# ADC.net
KiCad netlist of a schematic drawn in Altium Designer
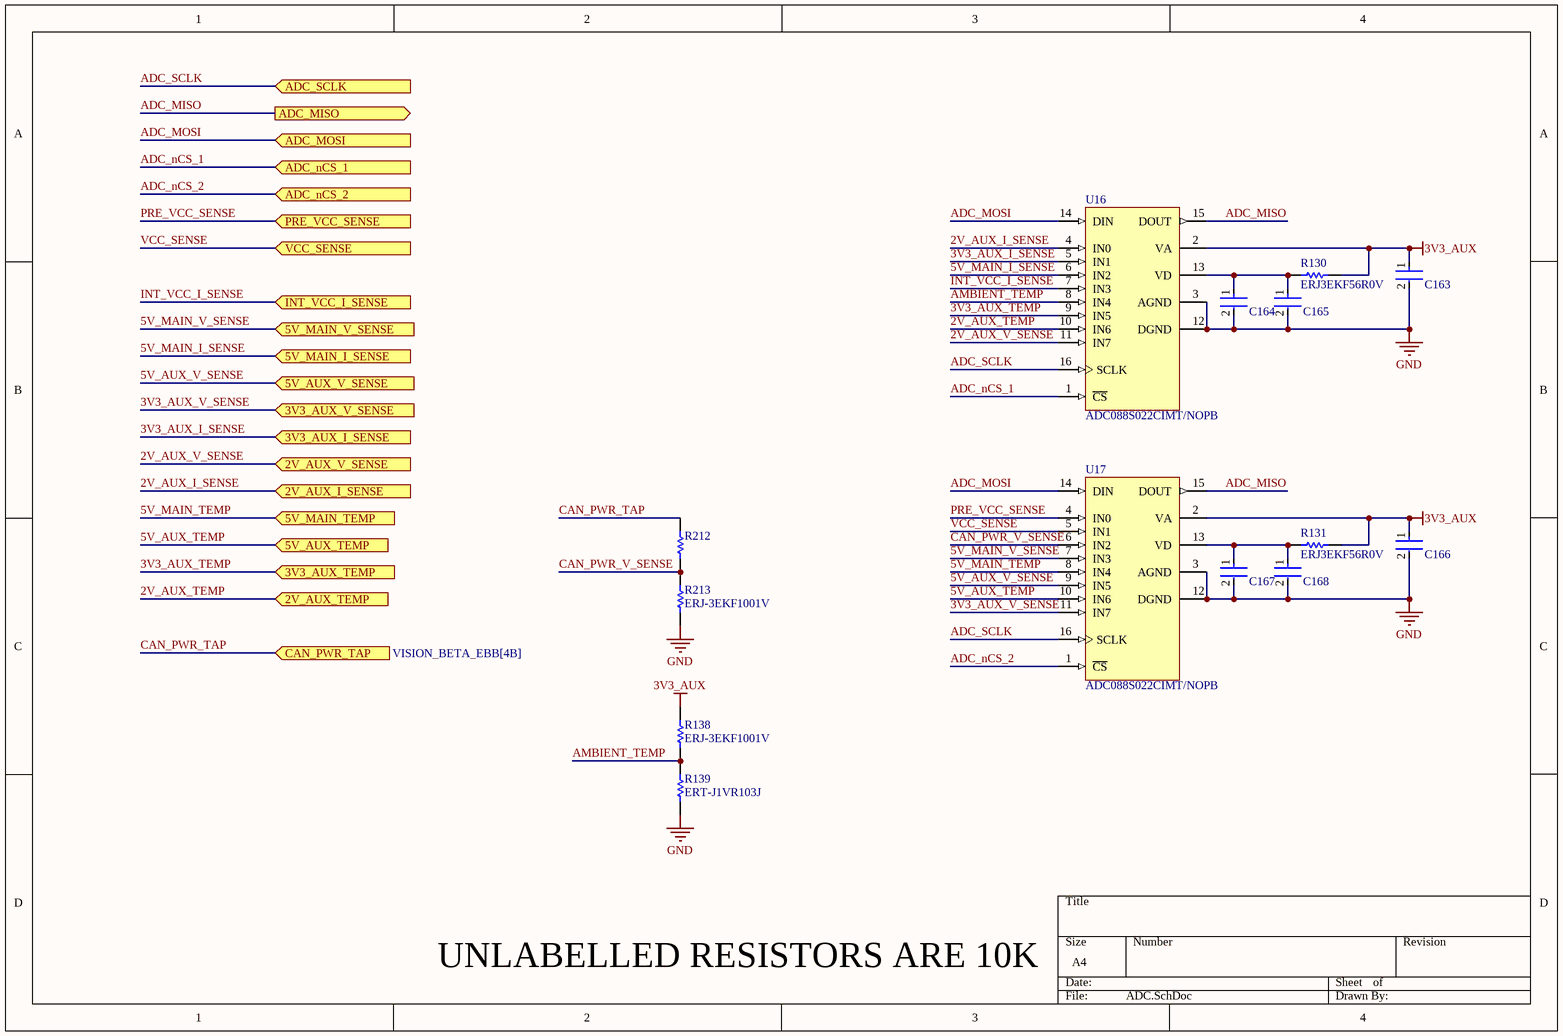
[diagram p0: ADC.SchDoc]

(export (version "E")
  (design (tool "Eeschema 10.0.6"))
  (components
    (comp (ref "C163")
      (value "C0402C104K8PACTU")
      (footprint "FP-C0402-BB-MFG")
      (description "CAP CER 0.1UF 10V X5R 0402")
      (fields (field (name "MANUFACTURER") "Kemet") (field (name "TOLERANCE") "0.1"))
      (libsource (lib "Altium Content Vault") (part "b4654b650e69147ec39a6b967a45e02"))
    )
    (comp (ref "C164")
      (value "C0402C104K8PACTU")
      (footprint "FP-C0402-BB-MFG")
      (description "CAP CER 0.1UF 10V X5R 0402")
      (fields (field (name "MANUFACTURER") "Kemet") (field (name "TOLERANCE") "0.1"))
      (libsource (lib "Altium Content Vault") (part "b4654b650e69147ec39a6b967a45e02"))
    )
    (comp (ref "C165")
      (value "C0402C104K8PACTU")
      (footprint "FP-C0402-BB-MFG")
      (description "CAP CER 0.1UF 10V X5R 0402")
      (fields (field (name "MANUFACTURER") "Kemet") (field (name "TOLERANCE") "0.1"))
      (libsource (lib "Altium Content Vault") (part "b4654b650e69147ec39a6b967a45e02"))
    )
    (comp (ref "C166")
      (value "C0402C104K8PACTU")
      (footprint "FP-C0402-BB-MFG")
      (description "CAP CER 0.1UF 10V X5R 0402")
      (fields (field (name "MANUFACTURER") "Kemet") (field (name "TOLERANCE") "0.1"))
      (libsource (lib "Altium Content Vault") (part "b4654b650e69147ec39a6b967a45e02"))
    )
    (comp (ref "C167")
      (value "C0402C104K8PACTU")
      (footprint "FP-C0402-BB-MFG")
      (description "CAP CER 0.1UF 10V X5R 0402")
      (fields (field (name "MANUFACTURER") "Kemet") (field (name "TOLERANCE") "0.1"))
      (libsource (lib "Altium Content Vault") (part "b4654b650e69147ec39a6b967a45e02"))
    )
    (comp (ref "C168")
      (value "C0402C104K8PACTU")
      (footprint "FP-C0402-BB-MFG")
      (description "CAP CER 0.1UF 10V X5R 0402")
      (fields (field (name "MANUFACTURER") "Kemet") (field (name "TOLERANCE") "0.1"))
      (libsource (lib "Altium Content Vault") (part "b4654b650e69147ec39a6b967a45e02"))
    )
    (comp (ref "R130")
      (value "ERJ3EKF56R0V")
      (footprint "RESC1608X55X30NL15T15")
      (fields (field (name "MANUFACTURER") "Panasonic"))
      (libsource (lib "Altium Content Vault") (part "RES"))
    )
    (comp (ref "R131")
      (value "ERJ3EKF56R0V")
      (footprint "RESC1608X55X30NL15T15")
      (fields (field (name "MANUFACTURER") "Panasonic"))
      (libsource (lib "Altium Content Vault") (part "RES"))
    )
    (comp (ref "R138")
      (value "ERJ-3EKF1001V")
      (footprint "RESC1608X55X30LL15T15")
      (fields (field (name "MANUFACTURER") "Panasonic"))
      (libsource (lib "Altium Content Vault") (part "RES"))
    )
    (comp (ref "R139")
      (value "ERT-J1VR103J")
      (footprint "RESC1608X90X30ML15T20")
      (fields (field (name "MANUFACTURER") "Panasonic"))
      (libsource (lib "Altium Content Vault") (part "RES"))
    )
    (comp (ref "R212")
      (value "ERJ3EKF1002V")
      (footprint "RESC1609X55X30LL15T15")
      (description "Chip Resistor, 10 KOhm, +/- 1%, 0.1 W, -55 to 155 degC, 0603 (1608 Metric), RoHS, Tape and Reel")
      (fields (field (name "TOLERANCE") "1%") (field (name "MANUFACTURER") "Panasonic"))
      (libsource (lib "Altium Content Vault") (part "RES-2"))
    )
    (comp (ref "R213")
      (value "ERJ-3EKF1001V")
      (footprint "RESC1608X55X30LL15T15")
      (fields (field (name "MANUFACTURER") "Panasonic"))
      (libsource (lib "Altium Content Vault") (part "RES"))
    )
    (comp (ref "U16")
      (value "ADC088S022CIMT/NOPB")
      (footprint "MTC16_L")
      (description "8-Channel, 50 kSPS to 200 kSPS, 8-Bit A/D Converter, 16-pin TSSOP, Pb-Free")
      (fields (field (name "MANUFACTURER") "National Semiconductor"))
      (libsource (lib "Altium Content Vault") (part "CON-ADC-ADC108S052CIMT"))
    )
    (comp (ref "U17")
      (value "ADC088S022CIMT/NOPB")
      (footprint "MTC16_L")
      (description "8-Channel, 50 kSPS to 200 kSPS, 8-Bit A/D Converter, 16-pin TSSOP, Pb-Free")
      (fields (field (name "MANUFACTURER") "National Semiconductor"))
      (libsource (lib "Altium Content Vault") (part "CON-ADC-ADC108S052CIMT"))
    )
  )
  (nets
    (net (code "1") (name "/2V_AUX_I_SENSE") (class "Default")
      (node (ref "U16") (pin "4") (pinfunction "IN0_4") (pintype "input"))
    )
    (net (code "2") (name "/2V_AUX_TEMP") (class "Default")
      (node (ref "U16") (pin "10") (pinfunction "IN6_10") (pintype "input"))
    )
    (net (code "3") (name "/2V_AUX_V_SENSE") (class "Default")
      (node (ref "U16") (pin "11") (pinfunction "IN7_11") (pintype "input"))
    )
    (net (code "4") (name "/3V3_AUX_I_SENSE") (class "Default")
      (node (ref "U16") (pin "5") (pinfunction "IN1_5") (pintype "input"))
    )
    (net (code "5") (name "/3V3_AUX_TEMP") (class "Default")
      (node (ref "U16") (pin "9") (pinfunction "IN5_9") (pintype "input"))
    )
    (net (code "6") (name "/3V3_AUX_V_SENSE") (class "Default")
      (node (ref "U17") (pin "11") (pinfunction "IN7_11") (pintype "input"))
    )
    (net (code "7") (name "/5V_AUX_TEMP") (class "Default")
      (node (ref "U17") (pin "10") (pinfunction "IN6_10") (pintype "input"))
    )
    (net (code "8") (name "/5V_AUX_V_SENSE") (class "Default")
      (node (ref "U17") (pin "9") (pinfunction "IN5_9") (pintype "input"))
    )
    (net (code "9") (name "/5V_MAIN_I_SENSE") (class "Default")
      (node (ref "U16") (pin "6") (pinfunction "IN2_6") (pintype "input"))
    )
    (net (code "10") (name "/5V_MAIN_TEMP") (class "Default")
      (node (ref "U17") (pin "8") (pinfunction "IN4_8") (pintype "input"))
    )
    (net (code "11") (name "/5V_MAIN_V_SENSE") (class "Default")
      (node (ref "U17") (pin "7") (pinfunction "IN3_7") (pintype "input"))
    )
    (net (code "12") (name "/ADC_MISO") (class "Default")
      (node (ref "U16") (pin "15") (pinfunction "DOUT_15") (pintype "output"))
      (node (ref "U17") (pin "15") (pinfunction "DOUT_15") (pintype "output"))
    )
    (net (code "13") (name "/ADC_MOSI") (class "Default")
      (node (ref "U16") (pin "14") (pinfunction "DIN_14") (pintype "input"))
      (node (ref "U17") (pin "14") (pinfunction "DIN_14") (pintype "input"))
    )
    (net (code "14") (name "/ADC_SCLK") (class "Default")
      (node (ref "U16") (pin "16") (pinfunction "SCLK_16") (pintype "input"))
      (node (ref "U17") (pin "16") (pinfunction "SCLK_16") (pintype "input"))
    )
    (net (code "15") (name "/ADC_nCS_1") (class "Default")
      (node (ref "U16") (pin "1") (pinfunction "~{CS}_1") (pintype "input"))
    )
    (net (code "16") (name "/ADC_nCS_2") (class "Default")
      (node (ref "U17") (pin "1") (pinfunction "~{CS}_1") (pintype "input"))
    )
    (net (code "17") (name "/AMBIENT_TEMP") (class "Default")
      (node (ref "R138") (pin "1") (pinfunction "1_1") (pintype "passive"))
      (node (ref "R139") (pin "2") (pinfunction "2_2") (pintype "passive"))
      (node (ref "U16") (pin "8") (pinfunction "IN4_8") (pintype "input"))
    )
    (net (code "18") (name "/CAN_PWR_TAP") (class "Default")
      (node (ref "R212") (pin "2") (pinfunction "2_2") (pintype "passive"))
    )
    (net (code "19") (name "/CAN_PWR_V_SENSE") (class "Default")
      (node (ref "R212") (pin "1") (pinfunction "1_1") (pintype "passive"))
      (node (ref "R213") (pin "2") (pinfunction "2_2") (pintype "passive"))
      (node (ref "U17") (pin "6") (pinfunction "IN2_6") (pintype "input"))
    )
    (net (code "20") (name "/INT_VCC_I_SENSE") (class "Default")
      (node (ref "U16") (pin "7") (pinfunction "IN3_7") (pintype "input"))
    )
    (net (code "21") (name "/PRE_VCC_SENSE") (class "Default")
      (node (ref "U17") (pin "4") (pinfunction "IN0_4") (pintype "input"))
    )
    (net (code "22") (name "/VCC_SENSE") (class "Default")
      (node (ref "U17") (pin "5") (pinfunction "IN1_5") (pintype "input"))
    )
    (net (code "23") (name "3V3_AUX") (class "Default")
      (node (ref "C163") (pin "1") (pinfunction "1_1") (pintype "passive"))
      (node (ref "C166") (pin "1") (pinfunction "1_1") (pintype "passive"))
      (node (ref "R130") (pin "1") (pinfunction "1_1") (pintype "passive"))
      (node (ref "R131") (pin "1") (pinfunction "1_1") (pintype "passive"))
      (node (ref "R138") (pin "2") (pinfunction "2_2") (pintype "passive"))
      (node (ref "U16") (pin "2") (pinfunction "VA_2") (pintype "power_in"))
      (node (ref "U17") (pin "2") (pinfunction "VA_2") (pintype "power_in"))
    )
    (net (code "24") (name "GND") (class "Default")
      (node (ref "C163") (pin "2") (pinfunction "2_2") (pintype "passive"))
      (node (ref "C164") (pin "2") (pinfunction "2_2") (pintype "passive"))
      (node (ref "C165") (pin "2") (pinfunction "2_2") (pintype "passive"))
      (node (ref "C166") (pin "2") (pinfunction "2_2") (pintype "passive"))
      (node (ref "C167") (pin "2") (pinfunction "2_2") (pintype "passive"))
      (node (ref "C168") (pin "2") (pinfunction "2_2") (pintype "passive"))
      (node (ref "R139") (pin "1") (pinfunction "1_1") (pintype "passive"))
      (node (ref "R213") (pin "1") (pinfunction "1_1") (pintype "passive"))
      (node (ref "U16") (pin "12") (pinfunction "DGND_12") (pintype "power_in"))
      (node (ref "U16") (pin "3") (pinfunction "AGND_3") (pintype "power_in"))
      (node (ref "U17") (pin "12") (pinfunction "DGND_12") (pintype "power_in"))
      (node (ref "U17") (pin "3") (pinfunction "AGND_3") (pintype "power_in"))
    )
    (net (code "25") (name "Net-(U16-VD)") (class "Default")
      (node (ref "C164") (pin "1") (pinfunction "1_1") (pintype "passive"))
      (node (ref "C165") (pin "1") (pinfunction "1_1") (pintype "passive"))
      (node (ref "R130") (pin "2") (pinfunction "2_2") (pintype "passive"))
      (node (ref "U16") (pin "13") (pinfunction "VD_13") (pintype "power_in"))
    )
    (net (code "26") (name "Net-(U17-VD)") (class "Default")
      (node (ref "C167") (pin "1") (pinfunction "1_1") (pintype "passive"))
      (node (ref "C168") (pin "1") (pinfunction "1_1") (pintype "passive"))
      (node (ref "R131") (pin "2") (pinfunction "2_2") (pintype "passive"))
      (node (ref "U17") (pin "13") (pinfunction "VD_13") (pintype "power_in"))
    )
  )
)
